# module_duino.net
KiCad netlist of a schematic drawn in EAGLE
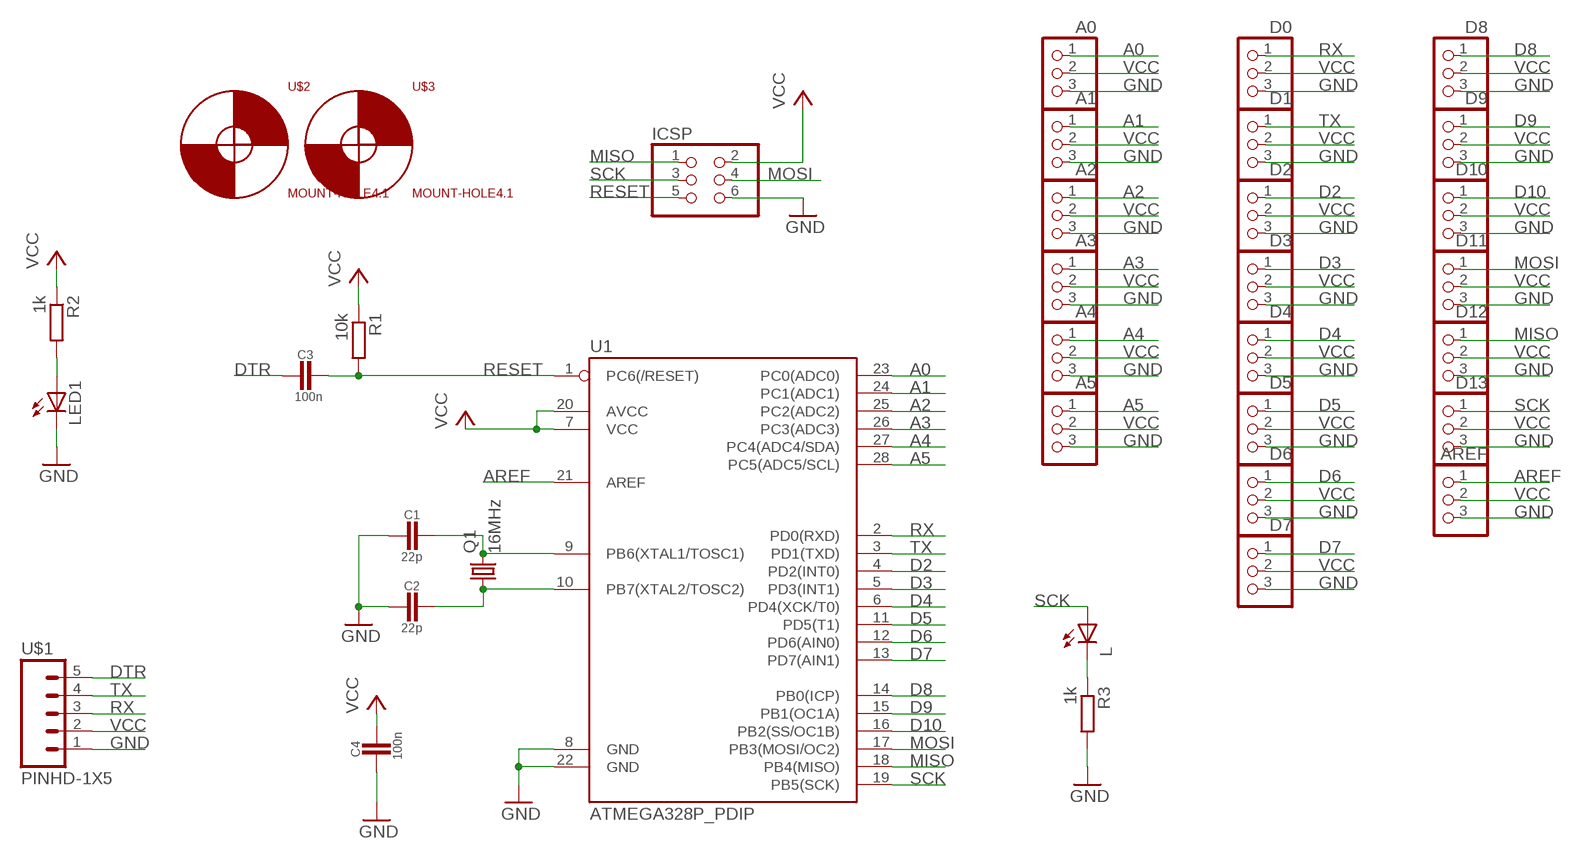
[diagram p0: schematic, sheet 1]

(export (version "E")
  (design (tool "Eeschema 10.0.6"))
  (components
    (comp (ref "A0")
      (value "PINHD-1X3")
      (footprint "eagle-import:1X03")
      (libsource (lib "eagle-import") (part "PINHD-1X3"))
    )
    (comp (ref "A1")
      (value "PINHD-1X3")
      (footprint "eagle-import:1X03")
      (libsource (lib "eagle-import") (part "PINHD-1X3"))
    )
    (comp (ref "A2")
      (value "PINHD-1X3")
      (footprint "eagle-import:1X03")
      (libsource (lib "eagle-import") (part "PINHD-1X3"))
    )
    (comp (ref "A3")
      (value "PINHD-1X3")
      (footprint "eagle-import:1X03")
      (libsource (lib "eagle-import") (part "PINHD-1X3"))
    )
    (comp (ref "A4")
      (value "PINHD-1X3")
      (footprint "eagle-import:1X03")
      (libsource (lib "eagle-import") (part "PINHD-1X3"))
    )
    (comp (ref "A5")
      (value "PINHD-1X3")
      (footprint "eagle-import:1X03")
      (libsource (lib "eagle-import") (part "PINHD-1X3"))
    )
    (comp (ref "AREF")
      (value "PINHD-1X3")
      (footprint "eagle-import:1X03")
      (libsource (lib "eagle-import") (part "PINHD-1X3"))
    )
    (comp (ref "C1")
      (value "22p")
      (footprint "eagle-import:CAP-PTH-5MM")
      (libsource (lib "eagle-import") (part "CAP"))
    )
    (comp (ref "C2")
      (value "22p")
      (footprint "eagle-import:CAP-PTH-5MM")
      (libsource (lib "eagle-import") (part "CAP"))
    )
    (comp (ref "C3")
      (value "100n")
      (footprint "eagle-import:CAP-PTH-5MM")
      (libsource (lib "eagle-import") (part "CAP"))
    )
    (comp (ref "C4")
      (value "100n")
      (footprint "eagle-import:CAP-PTH-5MM")
      (libsource (lib "eagle-import") (part "CAP"))
    )
    (comp (ref "D0")
      (value "PINHD-1X3")
      (footprint "eagle-import:1X03")
      (libsource (lib "eagle-import") (part "PINHD-1X3"))
    )
    (comp (ref "D1")
      (value "PINHD-1X3")
      (footprint "eagle-import:1X03")
      (libsource (lib "eagle-import") (part "PINHD-1X3"))
    )
    (comp (ref "D2")
      (value "PINHD-1X3")
      (footprint "eagle-import:1X03")
      (libsource (lib "eagle-import") (part "PINHD-1X3"))
    )
    (comp (ref "D3")
      (value "PINHD-1X3")
      (footprint "eagle-import:1X03")
      (libsource (lib "eagle-import") (part "PINHD-1X3"))
    )
    (comp (ref "D4")
      (value "PINHD-1X3")
      (footprint "eagle-import:1X03")
      (libsource (lib "eagle-import") (part "PINHD-1X3"))
    )
    (comp (ref "D5")
      (value "PINHD-1X3")
      (footprint "eagle-import:1X03")
      (libsource (lib "eagle-import") (part "PINHD-1X3"))
    )
    (comp (ref "D6")
      (value "PINHD-1X3")
      (footprint "eagle-import:1X03")
      (libsource (lib "eagle-import") (part "PINHD-1X3"))
    )
    (comp (ref "D7")
      (value "PINHD-1X3")
      (footprint "eagle-import:1X03")
      (libsource (lib "eagle-import") (part "PINHD-1X3"))
    )
    (comp (ref "D8")
      (value "PINHD-1X3")
      (footprint "eagle-import:1X03")
      (libsource (lib "eagle-import") (part "PINHD-1X3"))
    )
    (comp (ref "D9")
      (value "PINHD-1X3")
      (footprint "eagle-import:1X03")
      (libsource (lib "eagle-import") (part "PINHD-1X3"))
    )
    (comp (ref "D10")
      (value "PINHD-1X3")
      (footprint "eagle-import:1X03")
      (libsource (lib "eagle-import") (part "PINHD-1X3"))
    )
    (comp (ref "D11")
      (value "PINHD-1X3")
      (footprint "eagle-import:1X03")
      (libsource (lib "eagle-import") (part "PINHD-1X3"))
    )
    (comp (ref "D12")
      (value "PINHD-1X3")
      (footprint "eagle-import:1X03")
      (libsource (lib "eagle-import") (part "PINHD-1X3"))
    )
    (comp (ref "D13")
      (value "PINHD-1X3")
      (footprint "eagle-import:1X03")
      (libsource (lib "eagle-import") (part "PINHD-1X3"))
    )
    (comp (ref "ICSP")
      (value "PINHD-2X3")
      (footprint "eagle-import:2X03")
      (libsource (lib "eagle-import") (part "PINHD-2X3"))
    )
    (comp (ref "L")
      (value "LED5MM")
      (footprint "eagle-import:LED5MM")
      (libsource (lib "eagle-import") (part "LED5MM"))
    )
    (comp (ref "LED1")
      (value "LED5MM")
      (footprint "eagle-import:LED5MM")
      (libsource (lib "eagle-import") (part "LED5MM"))
    )
    (comp (ref "Q1")
      (value "16MHz")
      (footprint "eagle-import:HC49_S")
      (libsource (lib "eagle-import") (part "CRYSTAL"))
    )
    (comp (ref "R1")
      (value "10k")
      (footprint "eagle-import:0207_7")
      (libsource (lib "eagle-import") (part "R-EU_0207_7"))
    )
    (comp (ref "R2")
      (value "1k")
      (footprint "eagle-import:0207_7")
      (libsource (lib "eagle-import") (part "R-EU_0207_7"))
    )
    (comp (ref "R3")
      (value "1k")
      (footprint "eagle-import:0207_7")
      (libsource (lib "eagle-import") (part "R-EU_0207_7"))
    )
    (comp (ref "U$1")
      (value "PINHD-1X5")
      (footprint "eagle-import:1X05-CLEAN")
      (libsource (lib "eagle-import") (part "PINHD-1X5"))
    )
    (comp (ref "U$2")
      (value "MOUNT-HOLE4.1")
      (footprint "eagle-import:4.1")
      (libsource (lib "eagle-import") (part "MOUNT-HOLE4.1"))
    )
    (comp (ref "U$3")
      (value "MOUNT-HOLE4.1")
      (footprint "eagle-import:4.1")
      (libsource (lib "eagle-import") (part "MOUNT-HOLE4.1"))
    )
    (comp (ref "U1")
      (value "ATMEGA328P_PDIP")
      (footprint "eagle-import:DIL28-3")
      (libsource (lib "eagle-import") (part "ATMEGA328P_PDIP"))
    )
  )
  (nets
    (net (code "1") (name "/A0") (class "Default")
      (node (ref "A0") (pin "1") (pinfunction "1_1") (pintype "passive"))
      (node (ref "U1") (pin "23") (pinfunction "PC0(ADC0)_23") (pintype "bidirectional"))
    )
    (net (code "2") (name "/A1") (class "Default")
      (node (ref "A1") (pin "1") (pinfunction "1_1") (pintype "passive"))
      (node (ref "U1") (pin "24") (pinfunction "PC1(ADC1)_24") (pintype "bidirectional"))
    )
    (net (code "3") (name "/A2") (class "Default")
      (node (ref "A2") (pin "1") (pinfunction "1_1") (pintype "passive"))
      (node (ref "U1") (pin "25") (pinfunction "PC2(ADC2)_25") (pintype "bidirectional"))
    )
    (net (code "4") (name "/A3") (class "Default")
      (node (ref "A3") (pin "1") (pinfunction "1_1") (pintype "passive"))
      (node (ref "U1") (pin "26") (pinfunction "PC3(ADC3)_26") (pintype "bidirectional"))
    )
    (net (code "5") (name "/A4") (class "Default")
      (node (ref "A4") (pin "1") (pinfunction "1_1") (pintype "passive"))
      (node (ref "U1") (pin "27") (pinfunction "PC4(ADC4/SDA)_27") (pintype "bidirectional"))
    )
    (net (code "6") (name "/A5") (class "Default")
      (node (ref "A5") (pin "1") (pinfunction "1_1") (pintype "passive"))
      (node (ref "U1") (pin "28") (pinfunction "PC5(ADC5/SCL)_28") (pintype "bidirectional"))
    )
    (net (code "7") (name "/AREF") (class "Default")
      (node (ref "AREF") (pin "1") (pinfunction "1_1") (pintype "passive"))
      (node (ref "U1") (pin "21") (pinfunction "AREF_21") (pintype "bidirectional"))
    )
    (net (code "8") (name "/D2") (class "Default")
      (node (ref "D2") (pin "1") (pinfunction "1_1") (pintype "passive"))
      (node (ref "U1") (pin "4") (pinfunction "PD2(INT0)_4") (pintype "bidirectional"))
    )
    (net (code "9") (name "/D3") (class "Default")
      (node (ref "D3") (pin "1") (pinfunction "1_1") (pintype "passive"))
      (node (ref "U1") (pin "5") (pinfunction "PD3(INT1)_5") (pintype "bidirectional"))
    )
    (net (code "10") (name "/D4") (class "Default")
      (node (ref "D4") (pin "1") (pinfunction "1_1") (pintype "passive"))
      (node (ref "U1") (pin "6") (pinfunction "PD4(XCK/T0)_6") (pintype "bidirectional"))
    )
    (net (code "11") (name "/D5") (class "Default")
      (node (ref "D5") (pin "1") (pinfunction "1_1") (pintype "passive"))
      (node (ref "U1") (pin "11") (pinfunction "PD5(T1)_11") (pintype "bidirectional"))
    )
    (net (code "12") (name "/D6") (class "Default")
      (node (ref "D6") (pin "1") (pinfunction "1_1") (pintype "passive"))
      (node (ref "U1") (pin "12") (pinfunction "PD6(AIN0)_12") (pintype "bidirectional"))
    )
    (net (code "13") (name "/D7") (class "Default")
      (node (ref "D7") (pin "1") (pinfunction "1_1") (pintype "passive"))
      (node (ref "U1") (pin "13") (pinfunction "PD7(AIN1)_13") (pintype "bidirectional"))
    )
    (net (code "14") (name "/D8") (class "Default")
      (node (ref "D8") (pin "1") (pinfunction "1_1") (pintype "passive"))
      (node (ref "U1") (pin "14") (pinfunction "PB0(ICP)_14") (pintype "bidirectional"))
    )
    (net (code "15") (name "/D9") (class "Default")
      (node (ref "D9") (pin "1") (pinfunction "1_1") (pintype "passive"))
      (node (ref "U1") (pin "15") (pinfunction "PB1(OC1A)_15") (pintype "bidirectional"))
    )
    (net (code "16") (name "/D10") (class "Default")
      (node (ref "D10") (pin "1") (pinfunction "1_1") (pintype "passive"))
      (node (ref "U1") (pin "16") (pinfunction "PB2(SS/OC1B)_16") (pintype "bidirectional"))
    )
    (net (code "17") (name "/DTR") (class "Default")
      (node (ref "C3") (pin "1") (pinfunction "1_1") (pintype "bidirectional"))
      (node (ref "U$1") (pin "5") (pinfunction "5_5") (pintype "passive"))
    )
    (net (code "18") (name "/MISO") (class "Default")
      (node (ref "D12") (pin "1") (pinfunction "1_1") (pintype "passive"))
      (node (ref "ICSP") (pin "1") (pinfunction "1_1") (pintype "passive"))
      (node (ref "U1") (pin "18") (pinfunction "PB4(MISO)_18") (pintype "bidirectional"))
    )
    (net (code "19") (name "/MOSI") (class "Default")
      (node (ref "D11") (pin "1") (pinfunction "1_1") (pintype "passive"))
      (node (ref "ICSP") (pin "4") (pinfunction "4_4") (pintype "passive"))
      (node (ref "U1") (pin "17") (pinfunction "PB3(MOSI/OC2)_17") (pintype "bidirectional"))
    )
    (net (code "20") (name "/RESET") (class "Default")
      (node (ref "C3") (pin "2") (pinfunction "2_2") (pintype "bidirectional"))
      (node (ref "ICSP") (pin "5") (pinfunction "5_5") (pintype "passive"))
      (node (ref "R1") (pin "2") (pinfunction "2_2") (pintype "passive"))
      (node (ref "U1") (pin "1") (pinfunction "PC6(/RESET)_1") (pintype "bidirectional"))
    )
    (net (code "21") (name "/RX") (class "Default")
      (node (ref "D0") (pin "1") (pinfunction "1_1") (pintype "passive"))
      (node (ref "U$1") (pin "3") (pinfunction "3_3") (pintype "passive"))
      (node (ref "U1") (pin "2") (pinfunction "PD0(RXD)_2") (pintype "bidirectional"))
    )
    (net (code "22") (name "/SCK") (class "Default")
      (node (ref "D13") (pin "1") (pinfunction "1_1") (pintype "passive"))
      (node (ref "ICSP") (pin "3") (pinfunction "3_3") (pintype "passive"))
      (node (ref "L") (pin "A") (pinfunction "A_A") (pintype "passive"))
      (node (ref "U1") (pin "19") (pinfunction "PB5(SCK)_19") (pintype "bidirectional"))
    )
    (net (code "23") (name "/TX") (class "Default")
      (node (ref "D1") (pin "1") (pinfunction "1_1") (pintype "passive"))
      (node (ref "U$1") (pin "4") (pinfunction "4_4") (pintype "passive"))
      (node (ref "U1") (pin "3") (pinfunction "PD1(TXD)_3") (pintype "bidirectional"))
    )
    (net (code "24") (name "GND") (class "Default")
      (node (ref "A0") (pin "3") (pinfunction "3_3") (pintype "passive"))
      (node (ref "A1") (pin "3") (pinfunction "3_3") (pintype "passive"))
      (node (ref "A2") (pin "3") (pinfunction "3_3") (pintype "passive"))
      (node (ref "A3") (pin "3") (pinfunction "3_3") (pintype "passive"))
      (node (ref "A4") (pin "3") (pinfunction "3_3") (pintype "passive"))
      (node (ref "A5") (pin "3") (pinfunction "3_3") (pintype "passive"))
      (node (ref "AREF") (pin "3") (pinfunction "3_3") (pintype "passive"))
      (node (ref "C1") (pin "1") (pinfunction "1_1") (pintype "bidirectional"))
      (node (ref "C2") (pin "1") (pinfunction "1_1") (pintype "bidirectional"))
      (node (ref "C4") (pin "1") (pinfunction "1_1") (pintype "bidirectional"))
      (node (ref "D0") (pin "3") (pinfunction "3_3") (pintype "passive"))
      (node (ref "D1") (pin "3") (pinfunction "3_3") (pintype "passive"))
      (node (ref "D10") (pin "3") (pinfunction "3_3") (pintype "passive"))
      (node (ref "D11") (pin "3") (pinfunction "3_3") (pintype "passive"))
      (node (ref "D12") (pin "3") (pinfunction "3_3") (pintype "passive"))
      (node (ref "D13") (pin "3") (pinfunction "3_3") (pintype "passive"))
      (node (ref "D2") (pin "3") (pinfunction "3_3") (pintype "passive"))
      (node (ref "D3") (pin "3") (pinfunction "3_3") (pintype "passive"))
      (node (ref "D4") (pin "3") (pinfunction "3_3") (pintype "passive"))
      (node (ref "D5") (pin "3") (pinfunction "3_3") (pintype "passive"))
      (node (ref "D6") (pin "3") (pinfunction "3_3") (pintype "passive"))
      (node (ref "D7") (pin "3") (pinfunction "3_3") (pintype "passive"))
      (node (ref "D8") (pin "3") (pinfunction "3_3") (pintype "passive"))
      (node (ref "D9") (pin "3") (pinfunction "3_3") (pintype "passive"))
      (node (ref "ICSP") (pin "6") (pinfunction "6_6") (pintype "passive"))
      (node (ref "LED1") (pin "K") (pinfunction "C_K") (pintype "passive"))
      (node (ref "R3") (pin "2") (pinfunction "2_2") (pintype "passive"))
      (node (ref "U$1") (pin "1") (pinfunction "1_1") (pintype "passive"))
      (node (ref "U1") (pin "22") (pinfunction "GND_22") (pintype "bidirectional"))
      (node (ref "U1") (pin "8") (pinfunction "GND_8") (pintype "bidirectional"))
    )
    (net (code "25") (name "Net-(L-C)") (class "Default")
      (node (ref "L") (pin "K") (pinfunction "C_K") (pintype "passive"))
      (node (ref "R3") (pin "1") (pinfunction "1_1") (pintype "passive"))
    )
    (net (code "26") (name "Net-(LED1-PadA)") (class "Default")
      (node (ref "LED1") (pin "A") (pinfunction "A_A") (pintype "passive"))
      (node (ref "R2") (pin "2") (pinfunction "2_2") (pintype "passive"))
    )
    (net (code "27") (name "Net-(U1-PB6(XTAL1{slash}TOSC1))") (class "Default")
      (node (ref "C1") (pin "2") (pinfunction "2_2") (pintype "bidirectional"))
      (node (ref "Q1") (pin "2") (pinfunction "2_2") (pintype "passive"))
      (node (ref "U1") (pin "9") (pinfunction "PB6(XTAL1/TOSC1)_9") (pintype "bidirectional"))
    )
    (net (code "28") (name "Net-(U1-PB7(XTAL2{slash}TOSC2))") (class "Default")
      (node (ref "C2") (pin "2") (pinfunction "2_2") (pintype "bidirectional"))
      (node (ref "Q1") (pin "1") (pinfunction "1_1") (pintype "passive"))
      (node (ref "U1") (pin "10") (pinfunction "PB7(XTAL2/TOSC2)_10") (pintype "bidirectional"))
    )
    (net (code "29") (name "VCC") (class "Default")
      (node (ref "A0") (pin "2") (pinfunction "2_2") (pintype "passive"))
      (node (ref "A1") (pin "2") (pinfunction "2_2") (pintype "passive"))
      (node (ref "A2") (pin "2") (pinfunction "2_2") (pintype "passive"))
      (node (ref "A3") (pin "2") (pinfunction "2_2") (pintype "passive"))
      (node (ref "A4") (pin "2") (pinfunction "2_2") (pintype "passive"))
      (node (ref "A5") (pin "2") (pinfunction "2_2") (pintype "passive"))
      (node (ref "AREF") (pin "2") (pinfunction "2_2") (pintype "passive"))
      (node (ref "C4") (pin "2") (pinfunction "2_2") (pintype "bidirectional"))
      (node (ref "D0") (pin "2") (pinfunction "2_2") (pintype "passive"))
      (node (ref "D1") (pin "2") (pinfunction "2_2") (pintype "passive"))
      (node (ref "D10") (pin "2") (pinfunction "2_2") (pintype "passive"))
      (node (ref "D11") (pin "2") (pinfunction "2_2") (pintype "passive"))
      (node (ref "D12") (pin "2") (pinfunction "2_2") (pintype "passive"))
      (node (ref "D13") (pin "2") (pinfunction "2_2") (pintype "passive"))
      (node (ref "D2") (pin "2") (pinfunction "2_2") (pintype "passive"))
      (node (ref "D3") (pin "2") (pinfunction "2_2") (pintype "passive"))
      (node (ref "D4") (pin "2") (pinfunction "2_2") (pintype "passive"))
      (node (ref "D5") (pin "2") (pinfunction "2_2") (pintype "passive"))
      (node (ref "D6") (pin "2") (pinfunction "2_2") (pintype "passive"))
      (node (ref "D7") (pin "2") (pinfunction "2_2") (pintype "passive"))
      (node (ref "D8") (pin "2") (pinfunction "2_2") (pintype "passive"))
      (node (ref "D9") (pin "2") (pinfunction "2_2") (pintype "passive"))
      (node (ref "ICSP") (pin "2") (pinfunction "2_2") (pintype "passive"))
      (node (ref "R1") (pin "1") (pinfunction "1_1") (pintype "passive"))
      (node (ref "R2") (pin "1") (pinfunction "1_1") (pintype "passive"))
      (node (ref "U$1") (pin "2") (pinfunction "2_2") (pintype "passive"))
      (node (ref "U1") (pin "20") (pinfunction "AVCC_20") (pintype "bidirectional"))
      (node (ref "U1") (pin "7") (pinfunction "VCC_7") (pintype "bidirectional"))
    )
  )
)
